# Clocks.net
KiCad netlist of a schematic drawn in Altium Designer
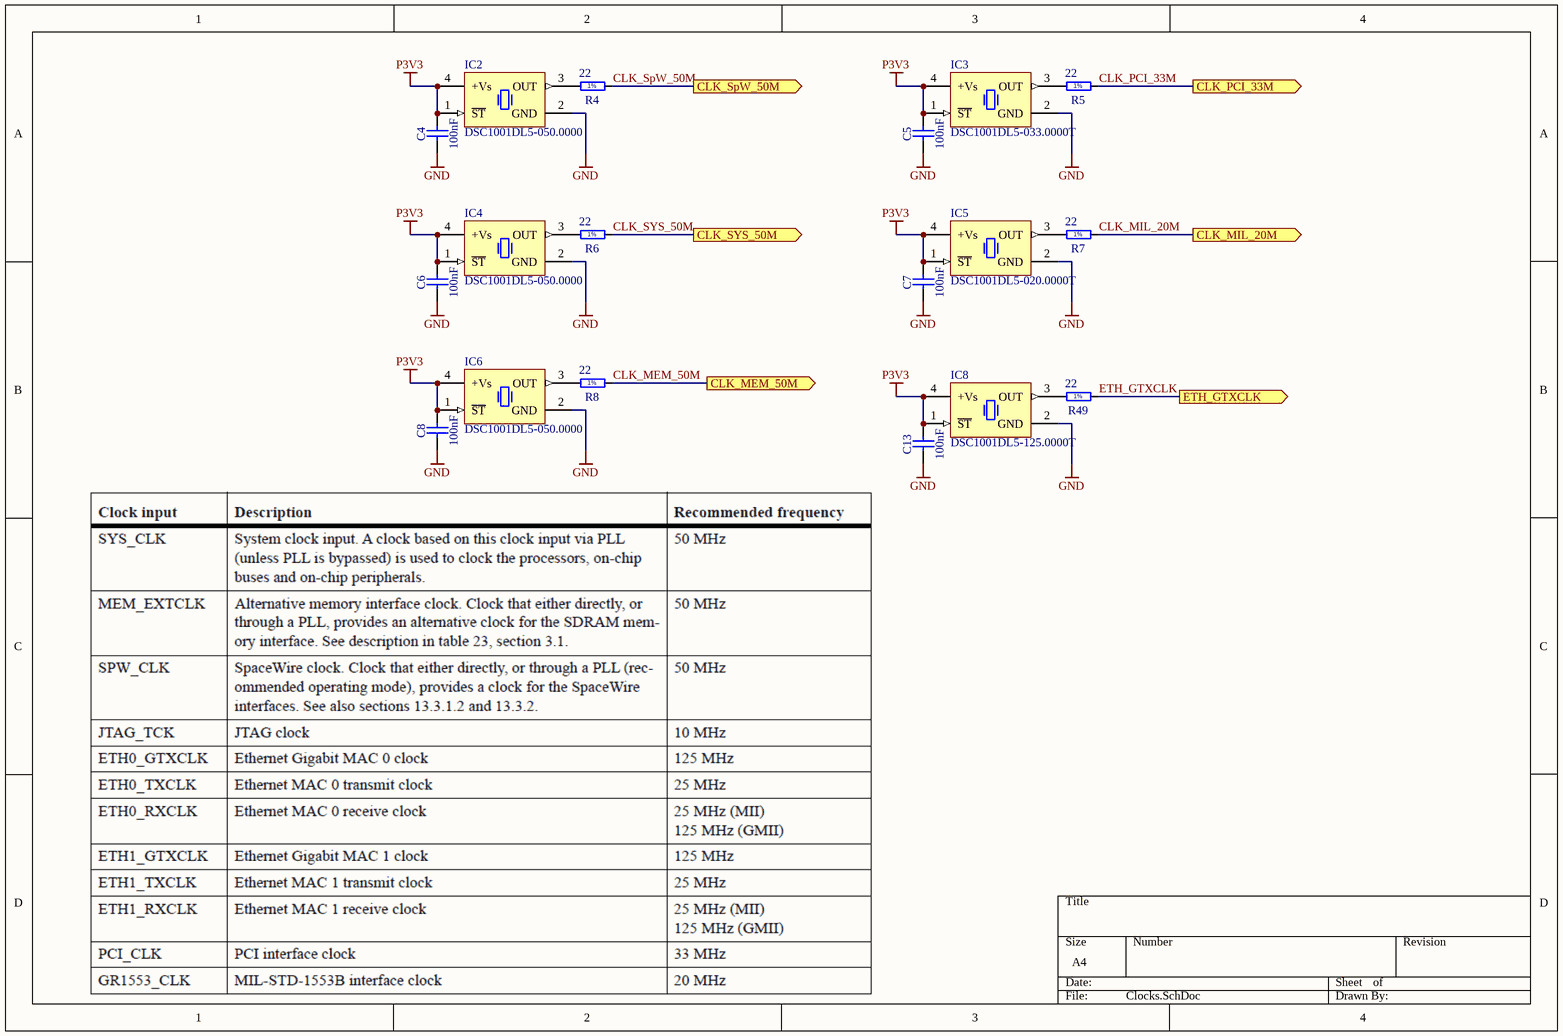
[diagram p0: Clocks.SchDoc]

(export (version "E")
  (design (tool "Eeschema 10.0.6"))
  (components
    (comp (ref "C4")
      (value "100nF")
      (footprint "CAPC0603X33N")
      (description "Non-polarised capacitor")
      (fields
        (field (name "PART NUMBER") "CC0201_100NF_6.3V_10%_X5R")
        (field (name "MANUFACTURER") "GENERIC")
        (field (name "AUTHOR") "CERN DEM JLC")
      )
      (libsource (lib "Capacitors") (part "Capacitor - non polarized"))
    )
    (comp (ref "C5")
      (value "100nF")
      (footprint "CAPC0603X33N")
      (description "Non-polarised capacitor")
      (fields
        (field (name "PART NUMBER") "CC0201_100NF_6.3V_10%_X5R")
        (field (name "MANUFACTURER") "GENERIC")
        (field (name "AUTHOR") "CERN DEM JLC")
      )
      (libsource (lib "Capacitors") (part "Capacitor - non polarized"))
    )
    (comp (ref "C6")
      (value "100nF")
      (footprint "CAPC0603X33N")
      (description "Non-polarised capacitor")
      (fields
        (field (name "PART NUMBER") "CC0201_100NF_6.3V_10%_X5R")
        (field (name "MANUFACTURER") "GENERIC")
        (field (name "AUTHOR") "CERN DEM JLC")
      )
      (libsource (lib "Capacitors") (part "Capacitor - non polarized"))
    )
    (comp (ref "C7")
      (value "100nF")
      (footprint "CAPC0603X33N")
      (description "Non-polarised capacitor")
      (fields
        (field (name "PART NUMBER") "CC0201_100NF_6.3V_10%_X5R")
        (field (name "MANUFACTURER") "GENERIC")
        (field (name "AUTHOR") "CERN DEM JLC")
      )
      (libsource (lib "Capacitors") (part "Capacitor - non polarized"))
    )
    (comp (ref "C8")
      (value "100nF")
      (footprint "CAPC0603X33N")
      (description "Non-polarised capacitor")
      (fields
        (field (name "PART NUMBER") "CC0201_100NF_6.3V_10%_X5R")
        (field (name "MANUFACTURER") "GENERIC")
        (field (name "AUTHOR") "CERN DEM JLC")
      )
      (libsource (lib "Capacitors") (part "Capacitor - non polarized"))
    )
    (comp (ref "C13")
      (value "100nF")
      (footprint "CAPC0603X33N")
      (description "Non-polarised capacitor")
      (fields
        (field (name "PART NUMBER") "CC0201_100NF_6.3V_10%_X5R")
        (field (name "MANUFACTURER") "GENERIC")
        (field (name "AUTHOR") "CERN DEM JLC")
      )
      (libsource (lib "Capacitors") (part "Capacitor - non polarized"))
    )
    (comp (ref "IC2")
      (value "DSC1001DL5-050.0000")
      (footprint "OSC_MICREL_2520")
      (description "MEMS 50MHz oscillator")
      (fields (field (name "MANUFACTURER") "Micrel"))
      (libsource (lib "LIBRARY_SCH") (part "OSC_DSC1001DL5-100.0000"))
    )
    (comp (ref "IC3")
      (value "DSC1001DL5-033.0000T")
      (footprint "OSC_MICREL_2520")
      (description "MEMS 33MHz oscillator")
      (fields (field (name "MANUFACTURER") "Micrel"))
      (libsource (lib "LIBRARY_SCH") (part "OSC_DSC1001DL5-100.0000"))
    )
    (comp (ref "IC4")
      (value "DSC1001DL5-050.0000")
      (footprint "OSC_MICREL_2520")
      (description "MEMS 50MHz oscillator")
      (fields (field (name "MANUFACTURER") "Micrel"))
      (libsource (lib "LIBRARY_SCH") (part "OSC_DSC1001DL5-100.0000"))
    )
    (comp (ref "IC5")
      (value "DSC1001DL5-020.0000T")
      (footprint "OSC_MICREL_2520")
      (description "MEMS 20MHz oscillator")
      (fields (field (name "MANUFACTURER") "Micrel"))
      (libsource (lib "LIBRARY_SCH") (part "OSC_DSC1001DL5-100.0000"))
    )
    (comp (ref "IC6")
      (value "DSC1001DL5-050.0000")
      (footprint "OSC_MICREL_2520")
      (description "MEMS 50MHz oscillator")
      (fields (field (name "MANUFACTURER") "Micrel"))
      (libsource (lib "LIBRARY_SCH") (part "OSC_DSC1001DL5-100.0000"))
    )
    (comp (ref "IC8")
      (value "DSC1001DL5-125.0000T")
      (footprint "OSC_MICREL_2520")
      (description "MEMS 125MHz oscillator")
      (fields (field (name "MANUFACTURER") "Micrel"))
      (libsource (lib "LIBRARY_SCH") (part "OSC_DSC1001DL5-100.0000"))
    )
    (comp (ref "R4")
      (value "22")
      (footprint "RESC1005X40N")
      (description "Resistor - 1%")
      (fields
        (field (name "PART NUMBER") "R0402_22R_1%_0.0625W_100PPM")
        (field (name "POWER") "0.0625W")
        (field (name "AUTHOR") "CERN DEM JLC")
      )
      (libsource (lib "Resistors") (part "Resistor - 1%"))
    )
    (comp (ref "R5")
      (value "22")
      (footprint "RESC1005X40N")
      (description "Resistor - 1%")
      (fields
        (field (name "PART NUMBER") "R0402_22R_1%_0.0625W_100PPM")
        (field (name "POWER") "0.0625W")
        (field (name "AUTHOR") "CERN DEM JLC")
      )
      (libsource (lib "Resistors") (part "Resistor - 1%"))
    )
    (comp (ref "R6")
      (value "22")
      (footprint "RESC1005X40N")
      (description "Resistor - 1%")
      (fields
        (field (name "PART NUMBER") "R0402_22R_1%_0.0625W_100PPM")
        (field (name "POWER") "0.0625W")
        (field (name "AUTHOR") "CERN DEM JLC")
      )
      (libsource (lib "Resistors") (part "Resistor - 1%"))
    )
    (comp (ref "R7")
      (value "22")
      (footprint "RESC1005X40N")
      (description "Resistor - 1%")
      (fields
        (field (name "PART NUMBER") "R0402_22R_1%_0.0625W_100PPM")
        (field (name "POWER") "0.0625W")
        (field (name "AUTHOR") "CERN DEM JLC")
      )
      (libsource (lib "Resistors") (part "Resistor - 1%"))
    )
    (comp (ref "R8")
      (value "22")
      (footprint "RESC1005X40N")
      (description "Resistor - 1%")
      (fields
        (field (name "PART NUMBER") "R0402_22R_1%_0.0625W_100PPM")
        (field (name "POWER") "0.0625W")
        (field (name "AUTHOR") "CERN DEM JLC")
      )
      (libsource (lib "Resistors") (part "Resistor - 1%"))
    )
    (comp (ref "R49")
      (value "22")
      (footprint "RESC1005X40N")
      (description "Resistor - 1%")
      (fields
        (field (name "PART NUMBER") "R0402_22R_1%_0.0625W_100PPM")
        (field (name "POWER") "0.0625W")
        (field (name "AUTHOR") "CERN DEM JLC")
      )
      (libsource (lib "Resistors") (part "Resistor - 1%"))
    )
  )
  (nets
    (net (code "1") (name "/CLK_MEM_50M") (class "Default")
      (node (ref "R8") (pin "2") (pinfunction "2_2") (pintype "passive"))
    )
    (net (code "2") (name "/CLK_MIL_20M") (class "Default")
      (node (ref "R7") (pin "2") (pinfunction "2_2") (pintype "passive"))
    )
    (net (code "3") (name "/CLK_PCI_33M") (class "Default")
      (node (ref "R5") (pin "2") (pinfunction "2_2") (pintype "passive"))
    )
    (net (code "4") (name "/CLK_SYS_50M") (class "Default")
      (node (ref "R6") (pin "2") (pinfunction "2_2") (pintype "passive"))
    )
    (net (code "5") (name "/CLK_SpW_50M") (class "Default")
      (node (ref "R4") (pin "2") (pinfunction "2_2") (pintype "passive"))
    )
    (net (code "6") (name "/ETH_GTXCLK") (class "Default")
      (node (ref "R49") (pin "2") (pinfunction "2_2") (pintype "passive"))
    )
    (net (code "7") (name "GND") (class "Default")
      (node (ref "C13") (pin "1") (pinfunction "1_1") (pintype "passive"))
      (node (ref "C4") (pin "1") (pinfunction "1_1") (pintype "passive"))
      (node (ref "C5") (pin "1") (pinfunction "1_1") (pintype "passive"))
      (node (ref "C6") (pin "1") (pinfunction "1_1") (pintype "passive"))
      (node (ref "C7") (pin "1") (pinfunction "1_1") (pintype "passive"))
      (node (ref "C8") (pin "1") (pinfunction "1_1") (pintype "passive"))
      (node (ref "IC2") (pin "2") (pinfunction "GND_2") (pintype "power_in"))
      (node (ref "IC3") (pin "2") (pinfunction "GND_2") (pintype "power_in"))
      (node (ref "IC4") (pin "2") (pinfunction "GND_2") (pintype "power_in"))
      (node (ref "IC5") (pin "2") (pinfunction "GND_2") (pintype "power_in"))
      (node (ref "IC6") (pin "2") (pinfunction "GND_2") (pintype "power_in"))
      (node (ref "IC8") (pin "2") (pinfunction "GND_2") (pintype "power_in"))
    )
    (net (code "8") (name "Net-(IC2-OUT)") (class "Default")
      (node (ref "IC2") (pin "3") (pinfunction "OUT_3") (pintype "output"))
      (node (ref "R4") (pin "1") (pinfunction "1_1") (pintype "passive"))
    )
    (net (code "9") (name "Net-(IC3-OUT)") (class "Default")
      (node (ref "IC3") (pin "3") (pinfunction "OUT_3") (pintype "output"))
      (node (ref "R5") (pin "1") (pinfunction "1_1") (pintype "passive"))
    )
    (net (code "10") (name "Net-(IC4-OUT)") (class "Default")
      (node (ref "IC4") (pin "3") (pinfunction "OUT_3") (pintype "output"))
      (node (ref "R6") (pin "1") (pinfunction "1_1") (pintype "passive"))
    )
    (net (code "11") (name "Net-(IC5-OUT)") (class "Default")
      (node (ref "IC5") (pin "3") (pinfunction "OUT_3") (pintype "output"))
      (node (ref "R7") (pin "1") (pinfunction "1_1") (pintype "passive"))
    )
    (net (code "12") (name "Net-(IC6-OUT)") (class "Default")
      (node (ref "IC6") (pin "3") (pinfunction "OUT_3") (pintype "output"))
      (node (ref "R8") (pin "1") (pinfunction "1_1") (pintype "passive"))
    )
    (net (code "13") (name "Net-(IC8-OUT)") (class "Default")
      (node (ref "IC8") (pin "3") (pinfunction "OUT_3") (pintype "output"))
      (node (ref "R49") (pin "1") (pinfunction "1_1") (pintype "passive"))
    )
    (net (code "14") (name "P3V3") (class "Default")
      (node (ref "C13") (pin "2") (pinfunction "2_2") (pintype "passive"))
      (node (ref "C4") (pin "2") (pinfunction "2_2") (pintype "passive"))
      (node (ref "C5") (pin "2") (pinfunction "2_2") (pintype "passive"))
      (node (ref "C6") (pin "2") (pinfunction "2_2") (pintype "passive"))
      (node (ref "C7") (pin "2") (pinfunction "2_2") (pintype "passive"))
      (node (ref "C8") (pin "2") (pinfunction "2_2") (pintype "passive"))
      (node (ref "IC2") (pin "1") (pinfunction "ST_1") (pintype "input"))
      (node (ref "IC2") (pin "4") (pinfunction "+Vs_4") (pintype "power_in"))
      (node (ref "IC3") (pin "1") (pinfunction "ST_1") (pintype "input"))
      (node (ref "IC3") (pin "4") (pinfunction "+Vs_4") (pintype "power_in"))
      (node (ref "IC4") (pin "1") (pinfunction "ST_1") (pintype "input"))
      (node (ref "IC4") (pin "4") (pinfunction "+Vs_4") (pintype "power_in"))
      (node (ref "IC5") (pin "1") (pinfunction "ST_1") (pintype "input"))
      (node (ref "IC5") (pin "4") (pinfunction "+Vs_4") (pintype "power_in"))
      (node (ref "IC6") (pin "1") (pinfunction "ST_1") (pintype "input"))
      (node (ref "IC6") (pin "4") (pinfunction "+Vs_4") (pintype "power_in"))
      (node (ref "IC8") (pin "1") (pinfunction "ST_1") (pintype "input"))
      (node (ref "IC8") (pin "4") (pinfunction "+Vs_4") (pintype "power_in"))
    )
  )
)
